# 13thISE_ver7.net
KiCad netlist of a schematic drawn in EAGLE
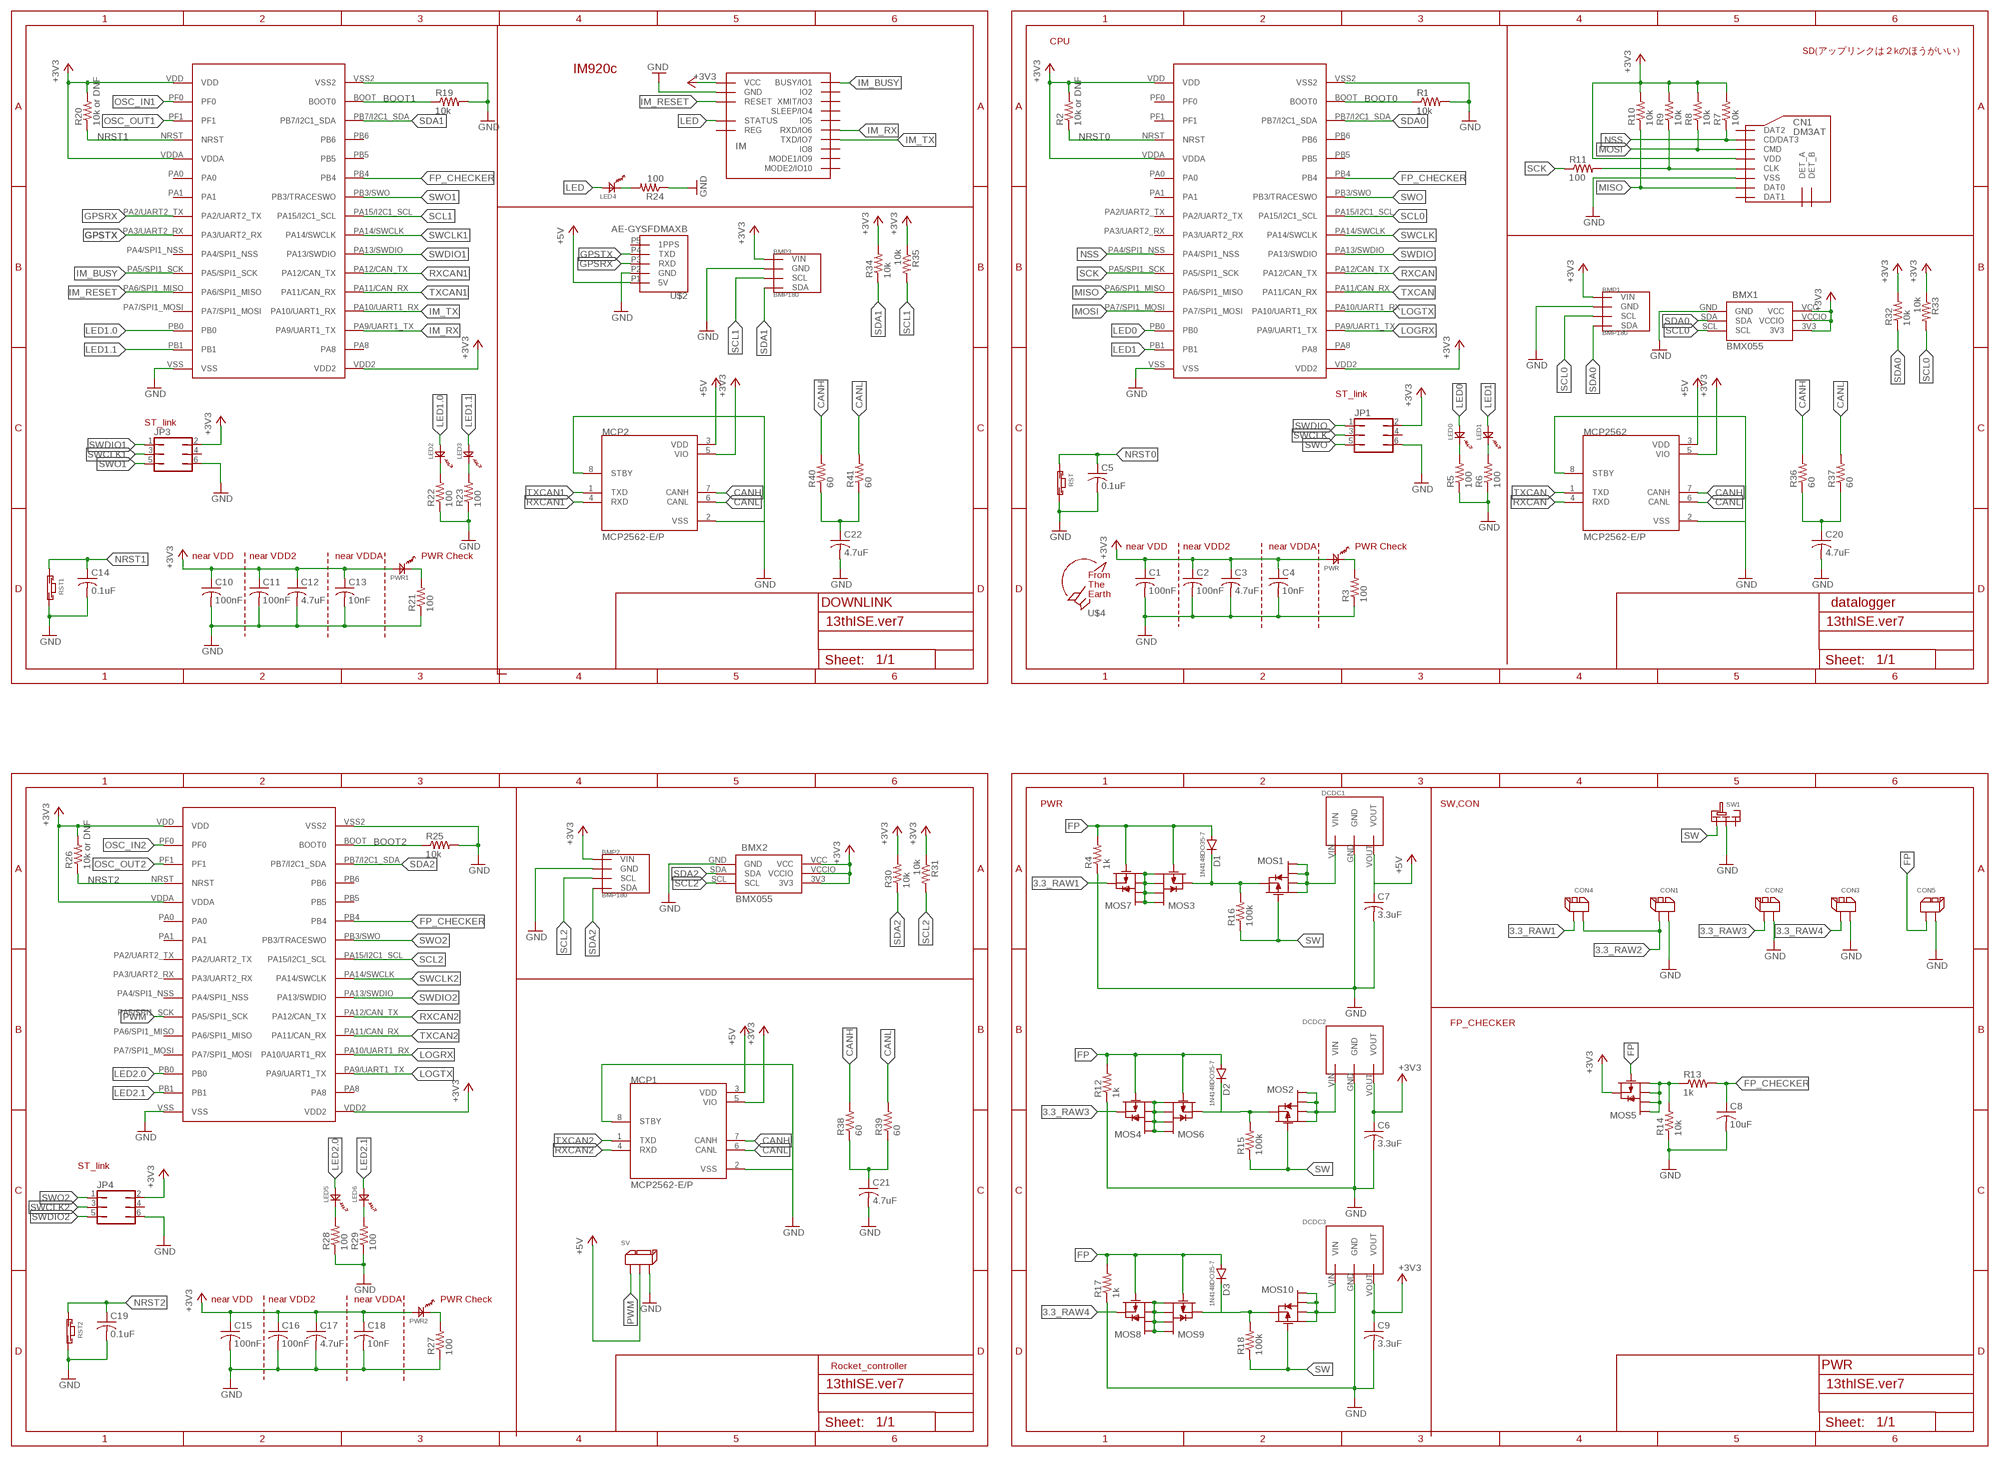
[diagram p0: schematic, sheet 1]

(export (version "E")
  (design (tool "Eeschema 10.0.6"))
  (components
    (comp (ref "BMP1")
      (value "BMP180")
      (footprint "eagle-import:GY-68")
      (libsource (lib "eagle-import") (part "BMP180"))
    )
    (comp (ref "BMP2")
      (value "BMP180")
      (footprint "eagle-import:GY-68")
      (libsource (lib "eagle-import") (part "BMP180"))
    )
    (comp (ref "BMP3")
      (value "BMP180")
      (footprint "eagle-import:GY-68")
      (libsource (lib "eagle-import") (part "BMP180"))
    )
    (comp (ref "BMX1")
      (value "BMX055")
      (footprint "eagle-import:BMX055")
      (libsource (lib "eagle-import") (part "BMX055"))
    )
    (comp (ref "BMX2")
      (value "BMX055")
      (footprint "eagle-import:BMX055")
      (libsource (lib "eagle-import") (part "BMX055"))
    )
    (comp (ref "C1")
      (value "100nF")
      (footprint "eagle-import:C1608")
      (libsource (lib "eagle-import") (part "C-USC1608"))
    )
    (comp (ref "C2")
      (value "100nF")
      (footprint "eagle-import:C1608")
      (libsource (lib "eagle-import") (part "C-USC1608"))
    )
    (comp (ref "C3")
      (value "4.7uF")
      (footprint "eagle-import:C1608")
      (libsource (lib "eagle-import") (part "C-USC1608"))
    )
    (comp (ref "C4")
      (value "10nF")
      (footprint "eagle-import:C1608")
      (libsource (lib "eagle-import") (part "C-USC1608"))
    )
    (comp (ref "C5")
      (value "0.1uF")
      (footprint "eagle-import:C1608")
      (libsource (lib "eagle-import") (part "C-USC1608"))
    )
    (comp (ref "C6")
      (value "3.3uF")
      (footprint "eagle-import:C0603")
      (libsource (lib "eagle-import") (part "C-USC0603"))
    )
    (comp (ref "C7")
      (value "3.3uF")
      (footprint "eagle-import:C0603")
      (libsource (lib "eagle-import") (part "C-USC0603"))
    )
    (comp (ref "C8")
      (value "10uF")
      (footprint "eagle-import:C0603")
      (libsource (lib "eagle-import") (part "C-USC0603"))
    )
    (comp (ref "C9")
      (value "3.3uF")
      (footprint "eagle-import:C0603")
      (libsource (lib "eagle-import") (part "C-USC0603"))
    )
    (comp (ref "C10")
      (value "100nF")
      (footprint "eagle-import:C1608")
      (libsource (lib "eagle-import") (part "C-USC1608"))
    )
    (comp (ref "C11")
      (value "100nF")
      (footprint "eagle-import:C1608")
      (libsource (lib "eagle-import") (part "C-USC1608"))
    )
    (comp (ref "C12")
      (value "4.7uF")
      (footprint "eagle-import:C1608")
      (libsource (lib "eagle-import") (part "C-USC1608"))
    )
    (comp (ref "C13")
      (value "10nF")
      (footprint "eagle-import:C1608")
      (libsource (lib "eagle-import") (part "C-USC1608"))
    )
    (comp (ref "C14")
      (value "0.1uF")
      (footprint "eagle-import:C1608")
      (libsource (lib "eagle-import") (part "C-USC1608"))
    )
    (comp (ref "C15")
      (value "100nF")
      (footprint "eagle-import:C1608")
      (libsource (lib "eagle-import") (part "C-USC1608"))
    )
    (comp (ref "C16")
      (value "100nF")
      (footprint "eagle-import:C1608")
      (libsource (lib "eagle-import") (part "C-USC1608"))
    )
    (comp (ref "C17")
      (value "4.7uF")
      (footprint "eagle-import:C1608")
      (libsource (lib "eagle-import") (part "C-USC1608"))
    )
    (comp (ref "C18")
      (value "10nF")
      (footprint "eagle-import:C1608")
      (libsource (lib "eagle-import") (part "C-USC1608"))
    )
    (comp (ref "C19")
      (value "0.1uF")
      (footprint "eagle-import:C1608")
      (libsource (lib "eagle-import") (part "C-USC1608"))
    )
    (comp (ref "C20")
      (value "4.7uF")
      (footprint "eagle-import:C0603")
      (libsource (lib "eagle-import") (part "C-USC0603"))
    )
    (comp (ref "C21")
      (value "4.7uF")
      (footprint "eagle-import:C0603")
      (libsource (lib "eagle-import") (part "C-USC0603"))
    )
    (comp (ref "C22")
      (value "4.7uF")
      (footprint "eagle-import:C0603")
      (libsource (lib "eagle-import") (part "C-USC0603"))
    )
    (comp (ref "CN1")
      (value "DM3AT")
      (footprint "eagle-import:DM3AT")
      (libsource (lib "eagle-import") (part "DM3AT"))
    )
    (comp (ref "CON1")
      (value "2PIN")
      (footprint "eagle-import:2PIN")
      (libsource (lib "eagle-import") (part "2PIN"))
    )
    (comp (ref "CON2")
      (value "2PIN")
      (footprint "eagle-import:2PIN")
      (libsource (lib "eagle-import") (part "2PIN"))
    )
    (comp (ref "CON3")
      (value "2PIN")
      (footprint "eagle-import:2PIN")
      (libsource (lib "eagle-import") (part "2PIN"))
    )
    (comp (ref "CON4")
      (value "2PIN")
      (footprint "eagle-import:2PIN")
      (libsource (lib "eagle-import") (part "2PIN"))
    )
    (comp (ref "CON5")
      (value "2PIN")
      (footprint "eagle-import:2PIN")
      (libsource (lib "eagle-import") (part "2PIN"))
    )
    (comp (ref "D1")
      (value "1N4148DO35-7")
      (footprint "eagle-import:DO35-7")
      (libsource (lib "eagle-import") (part "1N4148DO35-7"))
    )
    (comp (ref "D2")
      (value "1N4148DO35-7")
      (footprint "eagle-import:DO35-7")
      (libsource (lib "eagle-import") (part "1N4148DO35-7"))
    )
    (comp (ref "D3")
      (value "1N4148DO35-7")
      (footprint "eagle-import:DO35-7")
      (libsource (lib "eagle-import") (part "1N4148DO35-7"))
    )
    (comp (ref "DCDC1")
      (value "5V1A_M78AR05-1")
      (footprint "eagle-import:5V1A_M78AR05-1")
      (libsource (lib "eagle-import") (part "5V1A_M78AR05-1"))
    )
    (comp (ref "DCDC2")
      (value "3.3V1A_M78AR033-1")
      (footprint "eagle-import:3.3V1A_M78AR033-1")
      (libsource (lib "eagle-import") (part "3.3V1A_M78AR033-1"))
    )
    (comp (ref "DCDC3")
      (value "3.3V1A_M78AR033-1")
      (footprint "eagle-import:3.3V1A_M78AR033-1")
      (libsource (lib "eagle-import") (part "3.3V1A_M78AR033-1"))
    )
    (comp (ref "IM")
      (value "IM920C")
      (footprint "eagle-import:IM920C")
      (libsource (lib "eagle-import") (part "IM920C"))
    )
    (comp (ref "JP1")
      (value "JP3Q")
      (footprint "eagle-import:JP3Q")
      (libsource (lib "eagle-import") (part "JP3Q"))
    )
    (comp (ref "JP3")
      (value "JP3Q")
      (footprint "eagle-import:JP3Q")
      (libsource (lib "eagle-import") (part "JP3Q"))
    )
    (comp (ref "JP4")
      (value "JP3Q")
      (footprint "eagle-import:JP3Q")
      (libsource (lib "eagle-import") (part "JP3Q"))
    )
    (comp (ref "LED0")
      (value "OSXX1608C1A")
      (footprint "eagle-import:OSXX1608C1A")
      (libsource (lib "eagle-import") (part "OSXX1608C1A"))
    )
    (comp (ref "LED1")
      (value "OSXX1608C1A")
      (footprint "eagle-import:OSXX1608C1A")
      (libsource (lib "eagle-import") (part "OSXX1608C1A"))
    )
    (comp (ref "LED2")
      (value "OSXX1608C1A")
      (footprint "eagle-import:OSXX1608C1A")
      (libsource (lib "eagle-import") (part "OSXX1608C1A"))
    )
    (comp (ref "LED3")
      (value "OSXX1608C1A")
      (footprint "eagle-import:OSXX1608C1A")
      (libsource (lib "eagle-import") (part "OSXX1608C1A"))
    )
    (comp (ref "LED4")
      (value "OSXX1608C1A")
      (footprint "eagle-import:OSXX1608C1A")
      (libsource (lib "eagle-import") (part "OSXX1608C1A"))
    )
    (comp (ref "LED5")
      (value "OSXX1608C1A")
      (footprint "eagle-import:OSXX1608C1A")
      (libsource (lib "eagle-import") (part "OSXX1608C1A"))
    )
    (comp (ref "LED6")
      (value "OSXX1608C1A")
      (footprint "eagle-import:OSXX1608C1A")
      (libsource (lib "eagle-import") (part "OSXX1608C1A"))
    )
    (comp (ref "MCP1")
      (value "MCP2562-E/P")
      (footprint "eagle-import:DIP787W45P254L1016H533Q8")
      (fields (field (name "MF") "Microchip"))
      (libsource (lib "eagle-import") (part "MCP2562-E/P"))
    )
    (comp (ref "MCP2")
      (value "MCP2562-E/P")
      (footprint "eagle-import:DIP787W45P254L1016H533Q8")
      (fields (field (name "MF") "Microchip"))
      (libsource (lib "eagle-import") (part "MCP2562-E/P"))
    )
    (comp (ref "MCP2562")
      (value "MCP2562-E/P")
      (footprint "eagle-import:DIP787W45P254L1016H533Q8")
      (fields (field (name "MF") "Microchip"))
      (libsource (lib "eagle-import") (part "MCP2562-E/P"))
    )
    (comp (ref "MOS1")
      (value "PCH_SSM6J808R")
      (footprint "eagle-import:SSM6J808R")
      (libsource (lib "eagle-import") (part "PCH_SSM6J808R"))
    )
    (comp (ref "MOS2")
      (value "PCH_SSM6J808R")
      (footprint "eagle-import:SSM6J808R")
      (libsource (lib "eagle-import") (part "PCH_SSM6J808R"))
    )
    (comp (ref "MOS3")
      (value "PCH_SSM6J808R")
      (footprint "eagle-import:SSM6J808R")
      (libsource (lib "eagle-import") (part "PCH_SSM6J808R"))
    )
    (comp (ref "MOS4")
      (value "PCH_SSM6J808R")
      (footprint "eagle-import:SSM6J808R")
      (libsource (lib "eagle-import") (part "PCH_SSM6J808R"))
    )
    (comp (ref "MOS5")
      (value "PCH_SSM6J808R")
      (footprint "eagle-import:SSM6J808R")
      (libsource (lib "eagle-import") (part "PCH_SSM6J808R"))
    )
    (comp (ref "MOS6")
      (value "PCH_SSM6J808R")
      (footprint "eagle-import:SSM6J808R")
      (libsource (lib "eagle-import") (part "PCH_SSM6J808R"))
    )
    (comp (ref "MOS7")
      (value "PCH_SSM6J808R")
      (footprint "eagle-import:SSM6J808R")
      (libsource (lib "eagle-import") (part "PCH_SSM6J808R"))
    )
    (comp (ref "MOS8")
      (value "PCH_SSM6J808R")
      (footprint "eagle-import:SSM6J808R")
      (libsource (lib "eagle-import") (part "PCH_SSM6J808R"))
    )
    (comp (ref "MOS9")
      (value "PCH_SSM6J808R")
      (footprint "eagle-import:SSM6J808R")
      (libsource (lib "eagle-import") (part "PCH_SSM6J808R"))
    )
    (comp (ref "MOS10")
      (value "PCH_SSM6J808R")
      (footprint "eagle-import:SSM6J808R")
      (libsource (lib "eagle-import") (part "PCH_SSM6J808R"))
    )
    (comp (ref "PWR")
      (value "OSXX1608C1A")
      (footprint "eagle-import:OSXX1608C1A")
      (libsource (lib "eagle-import") (part "OSXX1608C1A"))
    )
    (comp (ref "PWR1")
      (value "OSXX1608C1A")
      (footprint "eagle-import:OSXX1608C1A")
      (libsource (lib "eagle-import") (part "OSXX1608C1A"))
    )
    (comp (ref "PWR2")
      (value "OSXX1608C1A")
      (footprint "eagle-import:OSXX1608C1A")
      (libsource (lib "eagle-import") (part "OSXX1608C1A"))
    )
    (comp (ref "R1")
      (value "10k")
      (footprint "eagle-import:R0603")
      (libsource (lib "eagle-import") (part "R-US_R0603"))
    )
    (comp (ref "R2")
      (value "10k or DNF")
      (footprint "eagle-import:R0603")
      (libsource (lib "eagle-import") (part "R-US_R0603"))
    )
    (comp (ref "R3")
      (value "100")
      (footprint "eagle-import:R0603")
      (libsource (lib "eagle-import") (part "R-US_R0603"))
    )
    (comp (ref "R4")
      (value "1k")
      (footprint "eagle-import:R0603")
      (libsource (lib "eagle-import") (part "R-US_R0603"))
    )
    (comp (ref "R5")
      (value "100")
      (footprint "eagle-import:R0603")
      (libsource (lib "eagle-import") (part "R-US_R0603"))
    )
    (comp (ref "R6")
      (value "100")
      (footprint "eagle-import:R0603")
      (libsource (lib "eagle-import") (part "R-US_R0603"))
    )
    (comp (ref "R7")
      (value "10k")
      (footprint "eagle-import:R0603")
      (libsource (lib "eagle-import") (part "R-US_R0603"))
    )
    (comp (ref "R8")
      (value "10k")
      (footprint "eagle-import:R0603")
      (libsource (lib "eagle-import") (part "R-US_R0603"))
    )
    (comp (ref "R9")
      (value "10k")
      (footprint "eagle-import:R0603")
      (libsource (lib "eagle-import") (part "R-US_R0603"))
    )
    (comp (ref "R10")
      (value "10k")
      (footprint "eagle-import:R0603")
      (libsource (lib "eagle-import") (part "R-US_R0603"))
    )
    (comp (ref "R11")
      (value "100")
      (footprint "eagle-import:R0603")
      (libsource (lib "eagle-import") (part "R-US_R0603"))
    )
    (comp (ref "R12")
      (value "1k")
      (footprint "eagle-import:R0603")
      (libsource (lib "eagle-import") (part "R-US_R0603"))
    )
    (comp (ref "R13")
      (value "1k")
      (footprint "eagle-import:R0603")
      (libsource (lib "eagle-import") (part "R-US_R0603"))
    )
    (comp (ref "R14")
      (value "10k")
      (footprint "eagle-import:R0603")
      (libsource (lib "eagle-import") (part "R-US_R0603"))
    )
    (comp (ref "R15")
      (value "100k")
      (footprint "eagle-import:R0603")
      (libsource (lib "eagle-import") (part "R-US_R0603"))
    )
    (comp (ref "R16")
      (value "100k")
      (footprint "eagle-import:R0603")
      (libsource (lib "eagle-import") (part "R-US_R0603"))
    )
    (comp (ref "R17")
      (value "1k")
      (footprint "eagle-import:R0603")
      (libsource (lib "eagle-import") (part "R-US_R0603"))
    )
    (comp (ref "R18")
      (value "100k")
      (footprint "eagle-import:R0603")
      (libsource (lib "eagle-import") (part "R-US_R0603"))
    )
    (comp (ref "R19")
      (value "10k")
      (footprint "eagle-import:R0603")
      (libsource (lib "eagle-import") (part "R-US_R0603"))
    )
    (comp (ref "R20")
      (value "10k or DNF")
      (footprint "eagle-import:R0603")
      (libsource (lib "eagle-import") (part "R-US_R0603"))
    )
    (comp (ref "R21")
      (value "100")
      (footprint "eagle-import:R0603")
      (libsource (lib "eagle-import") (part "R-US_R0603"))
    )
    (comp (ref "R22")
      (value "100")
      (footprint "eagle-import:R0603")
      (libsource (lib "eagle-import") (part "R-US_R0603"))
    )
    (comp (ref "R23")
      (value "100")
      (footprint "eagle-import:R0603")
      (libsource (lib "eagle-import") (part "R-US_R0603"))
    )
    (comp (ref "R24")
      (value "100")
      (footprint "eagle-import:R0603")
      (libsource (lib "eagle-import") (part "R-US_R0603"))
    )
    (comp (ref "R25")
      (value "10k")
      (footprint "eagle-import:R0603")
      (libsource (lib "eagle-import") (part "R-US_R0603"))
    )
    (comp (ref "R26")
      (value "10k or DNF")
      (footprint "eagle-import:R0603")
      (libsource (lib "eagle-import") (part "R-US_R0603"))
    )
    (comp (ref "R27")
      (value "100")
      (footprint "eagle-import:R0603")
      (libsource (lib "eagle-import") (part "R-US_R0603"))
    )
    (comp (ref "R28")
      (value "100")
      (footprint "eagle-import:R0603")
      (libsource (lib "eagle-import") (part "R-US_R0603"))
    )
    (comp (ref "R29")
      (value "100")
      (footprint "eagle-import:R0603")
      (libsource (lib "eagle-import") (part "R-US_R0603"))
    )
    (comp (ref "R30")
      (value "10k")
      (footprint "eagle-import:R0603")
      (libsource (lib "eagle-import") (part "R-US_R0603"))
    )
    (comp (ref "R31")
      (value "10k")
      (footprint "eagle-import:R0603")
      (libsource (lib "eagle-import") (part "R-US_R0603"))
    )
    (comp (ref "R32")
      (value "10k")
      (footprint "eagle-import:R0603")
      (libsource (lib "eagle-import") (part "R-US_R0603"))
    )
    (comp (ref "R33")
      (value "10k")
      (footprint "eagle-import:R0603")
      (libsource (lib "eagle-import") (part "R-US_R0603"))
    )
    (comp (ref "R34")
      (value "10k")
      (footprint "eagle-import:R0603")
      (libsource (lib "eagle-import") (part "R-US_R0603"))
    )
    (comp (ref "R35")
      (value "10k")
      (footprint "eagle-import:R0603")
      (libsource (lib "eagle-import") (part "R-US_R0603"))
    )
    (comp (ref "R36")
      (value "60")
      (footprint "eagle-import:R0603")
      (libsource (lib "eagle-import") (part "R-US_R0603"))
    )
    (comp (ref "R37")
      (value "60")
      (footprint "eagle-import:R0603")
      (libsource (lib "eagle-import") (part "R-US_R0603"))
    )
    (comp (ref "R38")
      (value "60")
      (footprint "eagle-import:R0603")
      (libsource (lib "eagle-import") (part "R-US_R0603"))
    )
    (comp (ref "R39")
      (value "60")
      (footprint "eagle-import:R0603")
      (libsource (lib "eagle-import") (part "R-US_R0603"))
    )
    (comp (ref "R40")
      (value "60")
      (footprint "eagle-import:R0603")
      (libsource (lib "eagle-import") (part "R-US_R0603"))
    )
    (comp (ref "R41")
      (value "60")
      (footprint "eagle-import:R0603")
      (libsource (lib "eagle-import") (part "R-US_R0603"))
    )
    (comp (ref "RST")
      (value "TVAF06-A020B-R")
      (footprint "eagle-import:TVAF06-A020B-R")
      (libsource (lib "eagle-import") (part "TVAF06-A020B-R"))
    )
    (comp (ref "RST1")
      (value "TVAF06-A020B-R")
      (footprint "eagle-import:TVAF06-A020B-R")
      (libsource (lib "eagle-import") (part "TVAF06-A020B-R"))
    )
    (comp (ref "RST2")
      (value "TVAF06-A020B-R")
      (footprint "eagle-import:TVAF06-A020B-R")
      (libsource (lib "eagle-import") (part "TVAF06-A020B-R"))
    )
    (comp (ref "STM0")
      (value "STM32F303K8")
      (footprint "eagle-import:STM32F303K8")
      (libsource (lib "eagle-import") (part "STM32F303K8"))
    )
    (comp (ref "STM1")
      (value "STM32F303K8")
      (footprint "eagle-import:STM32F303K8")
      (libsource (lib "eagle-import") (part "STM32F303K8"))
    )
    (comp (ref "SV")
      (value "3PIN")
      (footprint "eagle-import:3PIN")
      (libsource (lib "eagle-import") (part "3PIN"))
    )
    (comp (ref "SW1")
      (value "SRIDE_SWITCH")
      (footprint "eagle-import:SRIDE_SWITCH")
      (libsource (lib "eagle-import") (part "SRIDE_SWITCH"))
    )
    (comp (ref "U$1")
      (value "STM32F303K8")
      (footprint "eagle-import:STM32F303K8")
      (libsource (lib "eagle-import") (part "STM32F303K8"))
    )
    (comp (ref "U$2")
      (value "AE-GYSFDMAXB")
      (footprint "eagle-import:AE-GYSFDMAXB")
      (libsource (lib "eagle-import") (part "AE-GYSFDMAXB"))
    )
    (comp (ref "U$4")
      (value "F.T.E.LOGO")
      (footprint "eagle-import:LOGO")
      (libsource (lib "eagle-import") (part "F.T.E.LOGO"))
    )
  )
  (nets
    (net (code "1") (name "+3V3") (class "Default")
      (node (ref "BMP1") (pin "P1") (pinfunction "VIN_P1") (pintype "bidirectional"))
      (node (ref "BMP2") (pin "P1") (pinfunction "VIN_P1") (pintype "bidirectional"))
      (node (ref "BMP3") (pin "P1") (pinfunction "VIN_P1") (pintype "bidirectional"))
      (node (ref "BMX1") (pin "3V3") (pinfunction "3V3_3V3") (pintype "power_in"))
      (node (ref "BMX1") (pin "VCC") (pinfunction "VCC_VCC") (pintype "power_in"))
      (node (ref "BMX1") (pin "VCCIO") (pinfunction "VCCIO_VCCIO") (pintype "power_in"))
      (node (ref "BMX2") (pin "3V3") (pinfunction "3V3_3V3") (pintype "power_in"))
      (node (ref "BMX2") (pin "VCC") (pinfunction "VCC_VCC") (pintype "power_in"))
      (node (ref "BMX2") (pin "VCCIO") (pinfunction "VCCIO_VCCIO") (pintype "power_in"))
      (node (ref "C1") (pin "1") (pinfunction "1_1") (pintype "passive"))
      (node (ref "C10") (pin "1") (pinfunction "1_1") (pintype "passive"))
      (node (ref "C11") (pin "1") (pinfunction "1_1") (pintype "passive"))
      (node (ref "C12") (pin "1") (pinfunction "1_1") (pintype "passive"))
      (node (ref "C13") (pin "1") (pinfunction "1_1") (pintype "passive"))
      (node (ref "C15") (pin "1") (pinfunction "1_1") (pintype "passive"))
      (node (ref "C16") (pin "1") (pinfunction "1_1") (pintype "passive"))
      (node (ref "C17") (pin "1") (pinfunction "1_1") (pintype "passive"))
      (node (ref "C18") (pin "1") (pinfunction "1_1") (pintype "passive"))
      (node (ref "C2") (pin "1") (pinfunction "1_1") (pintype "passive"))
      (node (ref "C3") (pin "1") (pinfunction "1_1") (pintype "passive"))
      (node (ref "C4") (pin "1") (pinfunction "1_1") (pintype "passive"))
      (node (ref "C6") (pin "1") (pinfunction "1_1") (pintype "passive"))
      (node (ref "C9") (pin "1") (pinfunction "1_1") (pintype "passive"))
      (node (ref "CN1") (pin "VDD") (pinfunction "VDD_VDD") (pintype "bidirectional"))
      (node (ref "DCDC2") (pin "VOUT") (pinfunction "VOUT_VOUT") (pintype "bidirectional"))
      (node (ref "DCDC3") (pin "VOUT") (pinfunction "VOUT_VOUT") (pintype "bidirectional"))
      (node (ref "IM") (pin "$P17") (pinfunction "VCC_$P17") (pintype "bidirectional"))
      (node (ref "JP1") (pin "2") (pinfunction "2_2") (pintype "passive"))
      (node (ref "JP3") (pin "2") (pinfunction "2_2") (pintype "passive"))
      (node (ref "JP4") (pin "2") (pinfunction "2_2") (pintype "passive"))
      (node (ref "MCP1") (pin "5") (pinfunction "VIO_5") (pintype "power_in"))
      (node (ref "MCP2") (pin "5") (pinfunction "VIO_5") (pintype "power_in"))
      (node (ref "MCP2562") (pin "5") (pinfunction "VIO_5") (pintype "power_in"))
      (node (ref "MOS5") (pin "4") (pinfunction "4_4") (pintype "bidirectional"))
      (node (ref "PWR") (pin "AN") (pinfunction "AN_AN") (pintype "bidirectional"))
      (node (ref "PWR1") (pin "AN") (pinfunction "AN_AN") (pintype "bidirectional"))
      (node (ref "PWR2") (pin "AN") (pinfunction "AN_AN") (pintype "bidirectional"))
      (node (ref "R10") (pin "2") (pinfunction "2_2") (pintype "passive"))
      (node (ref "R2") (pin "2") (pinfunction "2_2") (pintype "passive"))
      (node (ref "R20") (pin "2") (pinfunction "2_2") (pintype "passive"))
      (node (ref "R26") (pin "2") (pinfunction "2_2") (pintype "passive"))
      (node (ref "R30") (pin "2") (pinfunction "2_2") (pintype "passive"))
      (node (ref "R31") (pin "1") (pinfunction "1_1") (pintype "passive"))
      (node (ref "R32") (pin "2") (pinfunction "2_2") (pintype "passive"))
      (node (ref "R33") (pin "1") (pinfunction "1_1") (pintype "passive"))
      (node (ref "R34") (pin "2") (pinfunction "2_2") (pintype "passive"))
      (node (ref "R35") (pin "1") (pinfunction "1_1") (pintype "passive"))
      (node (ref "R7") (pin "2") (pinfunction "2_2") (pintype "passive"))
      (node (ref "R8") (pin "2") (pinfunction "2_2") (pintype "passive"))
      (node (ref "R9") (pin "2") (pinfunction "2_2") (pintype "passive"))
      (node (ref "STM0") (pin "VDD") (pinfunction "VDD_VDD") (pintype "power_in"))
      (node (ref "STM0") (pin "VDD2") (pinfunction "VDD2_VDD2") (pintype "power_in"))
      (node (ref "STM0") (pin "VDDA") (pinfunction "VDDA_VDDA") (pintype "power_in"))
      (node (ref "STM1") (pin "VDD") (pinfunction "VDD_VDD") (pintype "power_in"))
      (node (ref "STM1") (pin "VDD2") (pinfunction "VDD2_VDD2") (pintype "power_in"))
      (node (ref "STM1") (pin "VDDA") (pinfunction "VDDA_VDDA") (pintype "power_in"))
      (node (ref "U$1") (pin "VDD") (pinfunction "VDD_VDD") (pintype "power_in"))
      (node (ref "U$1") (pin "VDD2") (pinfunction "VDD2_VDD2") (pintype "power_in"))
      (node (ref "U$1") (pin "VDDA") (pinfunction "VDDA_VDDA") (pintype "power_in"))
    )
    (net (code "2") (name "+5V") (class "Default")
      (node (ref "C7") (pin "1") (pinfunction "1_1") (pintype "passive"))
      (node (ref "DCDC1") (pin "VOUT") (pinfunction "VOUT_VOUT") (pintype "bidirectional"))
      (node (ref "MCP1") (pin "3") (pinfunction "VDD_3") (pintype "power_in"))
      (node (ref "MCP2") (pin "3") (pinfunction "VDD_3") (pintype "power_in"))
      (node (ref "MCP2562") (pin "3") (pinfunction "VDD_3") (pintype "power_in"))
      (node (ref "SV") (pin "P$2") (pinfunction "P$2_P$2") (pintype "bidirectional"))
      (node (ref "U$2") (pin "P1") (pinfunction "5V_P1") (pintype "bidirectional"))
    )
    (net (code "3") (name "/BOOT0") (class "Default")
      (node (ref "R1") (pin "1") (pinfunction "1_1") (pintype "passive"))
      (node (ref "STM0") (pin "BOOT") (pinfunction "BOOT0_BOOT") (pintype "bidirectional"))
    )
    (net (code "4") (name "/BOOT1") (class "Default")
      (node (ref "R19") (pin "1") (pinfunction "1_1") (pintype "passive"))
      (node (ref "STM1") (pin "BOOT") (pinfunction "BOOT0_BOOT") (pintype "bidirectional"))
    )
    (net (code "5") (name "/BOOT2") (class "Default")
      (node (ref "R25") (pin "1") (pinfunction "1_1") (pintype "passive"))
      (node (ref "U$1") (pin "BOOT") (pinfunction "BOOT0_BOOT") (pintype "bidirectional"))
    )
    (net (code "6") (name "3.3_RAW1") (class "Default")
      (node (ref "CON4") (pin "P$2") (pinfunction "P$2_P$2") (pintype "bidirectional"))
      (node (ref "MOS7") (pin "4") (pinfunction "4_4") (pintype "bidirectional"))
    )
    (net (code "7") (name "3.3_RAW2") (class "Default")
      (node (ref "CON1") (pin "P$2") (pinfunction "P$2_P$2") (pintype "bidirectional"))
      (node (ref "CON4") (pin "P$1") (pinfunction "P$1_P$1") (pintype "bidirectional"))
    )
    (net (code "8") (name "3.3_RAW3") (class "Default")
      (node (ref "CON2") (pin "P$2") (pinfunction "P$2_P$2") (pintype "bidirectional"))
      (node (ref "MOS4") (pin "4") (pinfunction "4_4") (pintype "bidirectional"))
    )
    (net (code "9") (name "3.3_RAW4") (class "Default")
      (node (ref "CON3") (pin "P$2") (pinfunction "P$2_P$2") (pintype "bidirectional"))
      (node (ref "MOS8") (pin "4") (pinfunction "4_4") (pintype "bidirectional"))
    )
    (net (code "10") (name "CANH") (class "Default")
      (node (ref "MCP1") (pin "7") (pinfunction "CANH_7") (pintype "bidirectional"))
      (node (ref "MCP2") (pin "7") (pinfunction "CANH_7") (pintype "bidirectional"))
      (node (ref "MCP2562") (pin "7") (pinfunction "CANH_7") (pintype "bidirectional"))
      (node (ref "R36") (pin "2") (pinfunction "2_2") (pintype "passive"))
      (node (ref "R38") (pin "2") (pinfunction "2_2") (pintype "passive"))
      (node (ref "R40") (pin "2") (pinfunction "2_2") (pintype "passive"))
    )
    (net (code "11") (name "CANL") (class "Default")
      (node (ref "MCP1") (pin "6") (pinfunction "CANL_6") (pintype "bidirectional"))
      (node (ref "MCP2") (pin "6") (pinfunction "CANL_6") (pintype "bidirectional"))
      (node (ref "MCP2562") (pin "6") (pinfunction "CANL_6") (pintype "bidirectional"))
      (node (ref "R37") (pin "2") (pinfunction "2_2") (pintype "passive"))
      (node (ref "R39") (pin "2") (pinfunction "2_2") (pintype "passive"))
      (node (ref "R41") (pin "2") (pinfunction "2_2") (pintype "passive"))
    )
    (net (code "12") (name "FP") (class "Default")
      (node (ref "CON5") (pin "P$1") (pinfunction "P$1_P$1") (pintype "bidirectional"))
      (node (ref "D1") (pin "A") (pinfunction "A_A") (pintype "passive"))
      (node (ref "D2") (pin "A") (pinfunction "A_A") (pintype "passive"))
      (node (ref "D3") (pin "A") (pinfunction "A_A") (pintype "passive"))
      (node (ref "MOS3") (pin "3") (pinfunction "3_3") (pintype "bidirectional"))
      (node (ref "MOS4") (pin "3") (pinfunction "3_3") (pintype "bidirectional"))
      (node (ref "MOS5") (pin "3") (pinfunction "3_3") (pintype "bidirectional"))
      (node (ref "MOS6") (pin "3") (pinfunction "3_3") (pintype "bidirectional"))
      (node (ref "MOS7") (pin "3") (pinfunction "3_3") (pintype "bidirectional"))
      (node (ref "MOS8") (pin "3") (pinfunction "3_3") (pintype "bidirectional"))
      (node (ref "MOS9") (pin "3") (pinfunction "3_3") (pintype "bidirectional"))
      (node (ref "R12") (pin "2") (pinfunction "2_2") (pintype "passive"))
      (node (ref "R17") (pin "2") (pinfunction "2_2") (pintype "passive"))
      (node (ref "R4") (pin "2") (pinfunction "2_2") (pintype "passive"))
    )
    (net (code "13") (name "FP_CHECKER") (class "Default")
      (node (ref "C8") (pin "1") (pinfunction "1_1") (pintype "passive"))
      (node (ref "R13") (pin "2") (pinfunction "2_2") (pintype "passive"))
      (node (ref "STM0") (pin "PB4") (pinfunction "PB4_PB4") (pintype "bidirectional"))
      (node (ref "STM1") (pin "PB4") (pinfunction "PB4_PB4") (pintype "bidirectional"))
      (node (ref "U$1") (pin "PB4") (pinfunction "PB4_PB4") (pintype "bidirectional"))
    )
    (net (code "14") (name "GND") (class "Default")
      (node (ref "BMP1") (pin "P2") (pinfunction "GND_P2") (pintype "bidirectional"))
      (node (ref "BMP2") (pin "P2") (pinfunction "GND_P2") (pintype "bidirectional"))
      (node (ref "BMP3") (pin "P2") (pinfunction "GND_P2") (pintype "bidirectional"))
      (node (ref "BMX1") (pin "GND") (pinfunction "GND_GND") (pintype "power_in"))
      (node (ref "BMX2") (pin "GND") (pinfunction "GND_GND") (pintype "power_in"))
      (node (ref "C1") (pin "2") (pinfunction "2_2") (pintype "passive"))
      (node (ref "C10") (pin "2") (pinfunction "2_2") (pintype "passive"))
      (node (ref "C11") (pin "2") (pinfunction "2_2") (pintype "passive"))
      (node (ref "C12") (pin "2") (pinfunction "2_2") (pintype "passive"))
      (node (ref "C13") (pin "2") (pinfunction "2_2") (pintype "passive"))
      (node (ref "C14") (pin "2") (pinfunction "2_2") (pintype "passive"))
      (node (ref "C15") (pin "2") (pinfunction "2_2") (pintype "passive"))
      (node (ref "C16") (pin "2") (pinfunction "2_2") (pintype "passive"))
      (node (ref "C17") (pin "2") (pinfunction "2_2") (pintype "passive"))
      (node (ref "C18") (pin "2") (pinfunction "2_2") (pintype "passive"))
      (node (ref "C19") (pin "2") (pinfunction "2_2") (pintype "passive"))
      (node (ref "C2") (pin "2") (pinfunction "2_2") (pintype "passive"))
      (node (ref "C20") (pin "2") (pinfunction "2_2") (pintype "passive"))
      (node (ref "C21") (pin "2") (pinfunction "2_2") (pintype "passive"))
      (node (ref "C22") (pin "2") (pinfunction "2_2") (pintype "passive"))
      (node (ref "C3") (pin "2") (pinfunction "2_2") (pintype "passive"))
      (node (ref "C4") (pin "2") (pinfunction "2_2") (pintype "passive"))
      (node (ref "C5") (pin "2") (pinfunction "2_2") (pintype "passive"))
      (node (ref "C6") (pin "2") (pinfunction "2_2") (pintype "passive"))
      (node (ref "C7") (pin "2") (pinfunction "2_2") (pintype "passive"))
      (node (ref "C8") (pin "2") (pinfunction "2_2") (pintype "passive"))
      (node (ref "C9") (pin "2") (pinfunction "2_2") (pintype "passive"))
      (node (ref "CN1") (pin "VSS") (pinfunction "VSS_VSS") (pintype "bidirectional"))
      (node (ref "CON1") (pin "P$1") (pinfunction "P$1_P$1") (pintype "bidirectional"))
      (node (ref "CON2") (pin "P$1") (pinfunction "P$1_P$1") (pintype "bidirectional"))
      (node (ref "CON3") (pin "P$1") (pinfunction "P$1_P$1") (pintype "bidirectional"))
      (node (ref "CON5") (pin "P$2") (pinfunction "P$2_P$2") (pintype "bidirectional"))
      (node (ref "DCDC1") (pin "GND") (pinfunction "GND_GND") (pintype "bidirectional"))
      (node (ref "DCDC2") (pin "GND") (pinfunction "GND_GND") (pintype "bidirectional"))
      (node (ref "DCDC3") (pin "GND") (pinfunction "GND_GND") (pintype "bidirectional"))
      (node (ref "IM") (pin "$P18") (pinfunction "GND_$P18") (pintype "bidirectional"))
      (node (ref "JP1") (pin "6") (pinfunction "6_6") (pintype "passive"))
      (node (ref "JP3") (pin "6") (pinfunction "6_6") (pintype "passive"))
      (node (ref "JP4") (pin "6") (pinfunction "6_6") (pintype "passive"))
      (node (ref "MCP1") (pin "2") (pinfunction "VSS_2") (pintype "power_in"))
      (node (ref "MCP1") (pin "8") (pinfunction "STBY_8") (pintype "input"))
      (node (ref "MCP2") (pin "2") (pinfunction "VSS_2") (pintype "power_in"))
      (node (ref "MCP2") (pin "8") (pinfunction "STBY_8") (pintype "input"))
      (node (ref "MCP2562") (pin "2") (pinfunction "VSS_2") (pintype "power_in"))
      (node (ref "MCP2562") (pin "8") (pinfunction "STBY_8") (pintype "input"))
      (node (ref "R1") (pin "2") (pinfunction "2_2") (pintype "passive"))
      (node (ref "R12") (pin "1") (pinfunction "1_1") (pintype "passive"))
      (node (ref "R14") (pin "1") (pinfunction "1_1") (pintype "passive"))
      (node (ref "R17") (pin "1") (pinfunction "1_1") (pintype "passive"))
      (node (ref "R19") (pin "2") (pinfunction "2_2") (pintype "passive"))
      (node (ref "R21") (pin "1") (pinfunction "1_1") (pintype "passive"))
      (node (ref "R22") (pin "1") (pinfunction "1_1") (pintype "passive"))
      (node (ref "R23") (pin "1") (pinfunction "1_1") (pintype "passive"))
      (node (ref "R24") (pin "1") (pinfunction "1_1") (pintype "passive"))
      (node (ref "R25") (pin "2") (pinfunction "2_2") (pintype "passive"))
      (node (ref "R27") (pin "1") (pinfunction "1_1") (pintype "passive"))
      (node (ref "R28") (pin "1") (pinfunction "1_1") (pintype "passive"))
      (node (ref "R29") (pin "1") (pinfunction "1_1") (pintype "passive"))
      (node (ref "R3") (pin "1") (pinfunction "1_1") (pintype "passive"))
      (node (ref "R4") (pin "1") (pinfunction "1_1") (pintype "passive"))
      (node (ref "R5") (pin "1") (pinfunction "1_1") (pintype "passive"))
      (node (ref "R6") (pin "1") (pinfunction "1_1") (pintype "passive"))
      (node (ref "RST") (pin "P$2") (pinfunction "P$2_P$2") (pintype "bidirectional"))
      (node (ref "RST1") (pin "P$2") (pinfunction "P$2_P$2") (pintype "bidirectional"))
      (node (ref "RST2") (pin "P$2") (pinfunction "P$2_P$2") (pintype "bidirectional"))
      (node (ref "STM0") (pin "VSS") (pinfunction "VSS_VSS") (pintype "power_in"))
      (node (ref "STM0") (pin "VSS2") (pinfunction "VSS2_VSS2") (pintype "power_in"))
      (node (ref "STM1") (pin "VSS") (pinfunction "VSS_VSS") (pintype "power_in"))
      (node (ref "STM1") (pin "VSS2") (pinfunction "VSS2_VSS2") (pintype "power_in"))
      (node (ref "SV") (pin "P$3") (pinfunction "P$3_P$3") (pintype "bidirectional"))
      (node (ref "SW1") (pin "LR") (pinfunction "LR_LR") (pintype "bidirectional"))
      (node (ref "U$1") (pin "VSS") (pinfunction "VSS_VSS") (pintype "power_in"))
      (node (ref "U$1") (pin "VSS2") (pinfunction "VSS2_VSS2") (pintype "power_in"))
      (node (ref "U$2") (pin "P2") (pinfunction "GND_P2") (pintype "bidirectional"))
    )
    (net (code "15") (name "GPSRX") (class "Default")
      (node (ref "STM1") (pin "PA2/UART2_TX") (pinfunction "PA2/UART2_TX_PA2/UART2_TX") (pintype "bidirectional"))
      (node (ref "U$2") (pin "P3") (pinfunction "RXD_P3") (pintype "bidirectional"))
    )
    (net (code "16") (name "GPSTX") (class "Default")
      (node (ref "STM1") (pin "PA3/UART2_RX") (pinfunction "PA3/UART2_RX_PA3/UART2_RX") (pintype "bidirectional"))
      (node (ref "U$2") (pin "P4") (pinfunction "TXD_P4") (pintype "bidirectional"))
    )
    (net (code "17") (name "IM_BUSY") (class "Default")
      (node (ref "IM") (pin "$P1") (pinfunction "BUSY/IO1_$P1") (pintype "bidirectional"))
      (node (ref "STM1") (pin "PA5/SPI1_SCK") (pinfunction "PA5/SPI1_SCK_PA5/SPI1_SCK") (pintype "bidirectional"))
    )
    (net (code "18") (name "IM_RESET") (class "Default")
      (node (ref "IM") (pin "$P19") (pinfunction "RESET_$P19") (pintype "bidirectional"))
      (node (ref "STM1") (pin "PA6/SPI1_MISO") (pinfunction "PA6/SPI1_MISO_PA6/SPI1_MISO") (pintype "bidirectional"))
    )
    (net (code "19") (name "IM_RX") (class "Default")
      (node (ref "IM") (pin "$P6") (pinfunction "RXD/IO6_$P6") (pintype "bidirectional"))
      (node (ref "STM1") (pin "PA9/UART1_TX") (pinfunction "PA9/UART1_TX_PA9/UART1_TX") (pintype "bidirectional"))
    )
    (net (code "20") (name "IM_TX") (class "Default")
      (node (ref "IM") (pin "$P7") (pinfunction "TXD/IO7_$P7") (pintype "bidirectional"))
      (node (ref "STM1") (pin "PA10/UART1_RX") (pinfunction "PA10/UART1_RX_PA10/UART1_RX") (pintype "bidirectional"))
    )
    (net (code "21") (name "LED") (class "Default")
      (node (ref "IM") (pin "$P15") (pinfunction "STATUS_$P15") (pintype "bidirectional"))
      (node (ref "LED4") (pin "AN") (pinfunction "AN_AN") (pintype "bidirectional"))
    )
    (net (code "22") (name "LED0") (class "Default")
      (node (ref "LED0") (pin "AN") (pinfunction "AN_AN") (pintype "bidirectional"))
      (node (ref "STM0") (pin "PB0") (pinfunction "PB0_PB0") (pintype "bidirectional"))
    )
    (net (code "23") (name "LED1") (class "Default")
      (node (ref "LED1") (pin "AN") (pinfunction "AN_AN") (pintype "bidirectional"))
      (node (ref "STM0") (pin "PB1") (pinfunction "PB1_PB1") (pintype "bidirectional"))
    )
    (net (code "24") (name "LED1.0") (class "Default")
      (node (ref "LED2") (pin "AN") (pinfunction "AN_AN") (pintype "bidirectional"))
      (node (ref "STM1") (pin "PB0") (pinfunction "PB0_PB0") (pintype "bidirectional"))
    )
    (net (code "25") (name "LED1.1") (class "Default")
      (node (ref "LED3") (pin "AN") (pinfunction "AN_AN") (pintype "bidirectional"))
      (node (ref "STM1") (pin "PB1") (pinfunction "PB1_PB1") (pintype "bidirectional"))
    )
    (net (code "26") (name "LED2.0") (class "Default")
      (node (ref "LED5") (pin "AN") (pinfunction "AN_AN") (pintype "bidirectional"))
      (node (ref "U$1") (pin "PB0") (pinfunction "PB0_PB0") (pintype "bidirectional"))
    )
    (net (code "27") (name "LED2.1") (class "Default")
      (node (ref "LED6") (pin "AN") (pinfunction "AN_AN") (pintype "bidirectional"))
      (node (ref "U$1") (pin "PB1") (pinfunction "PB1_PB1") (pintype "bidirectional"))
    )
    (net (code "28") (name "LOGRX") (class "Default")
      (node (ref "STM0") (pin "PA9/UART1_TX") (pinfunction "PA9/UART1_TX_PA9/UART1_TX") (pintype "bidirectional"))
      (node (ref "U$1") (pin "PA10/UART1_RX") (pinfunction "PA10/UART1_RX_PA10/UART1_RX") (pintype "bidirectional"))
    )
    (net (code "29") (name "LOGTX") (class "Default")
      (node (ref "STM0") (pin "PA10/UART1_RX") (pinfunction "PA10/UART1_RX_PA10/UART1_RX") (pintype "bidirectional"))
      (node (ref "U$1") (pin "PA9/UART1_TX") (pinfunction "PA9/UART1_TX_PA9/UART1_TX") (pintype "bidirectional"))
    )
    (net (code "30") (name "MISO") (class "Default")
      (node (ref "CN1") (pin "DAT0") (pinfunction "DAT0_DAT0") (pintype "bidirectional"))
      (node (ref "R10") (pin "1") (pinfunction "1_1") (pintype "passive"))
      (node (ref "STM0") (pin "PA6/SPI1_MISO") (pinfunction "PA6/SPI1_MISO_PA6/SPI1_MISO") (pintype "bidirectional"))
    )
    (net (code "31") (name "MOSI") (class "Default")
      (node (ref "CN1") (pin "CMD") (pinfunction "CMD_CMD") (pintype "bidirectional"))
      (node (ref "R8") (pin "1") (pinfunction "1_1") (pintype "passive"))
      (node (ref "STM0") (pin "PA7/SPI1_MOSI") (pinfunction "PA7/SPI1_MOSI_PA7/SPI1_MOSI") (pintype "bidirectional"))
    )
    (net (code "32") (name "NRST0") (class "Default")
      (node (ref "C5") (pin "1") (pinfunction "1_1") (pintype "passive"))
      (node (ref "R2") (pin "1") (pinfunction "1_1") (pintype "passive"))
      (node (ref "RST") (pin "P$1") (pinfunction "P$1_P$1") (pintype "bidirectional"))
      (node (ref "STM0") (pin "NRST") (pinfunction "NRST_NRST") (pintype "bidirectional"))
    )
    (net (code "33") (name "NRST1") (class "Default")
      (node (ref "C14") (pin "1") (pinfunction "1_1") (pintype "passive"))
      (node (ref "R20") (pin "1") (pinfunction "1_1") (pintype "passive"))
      (node (ref "RST1") (pin "P$1") (pinfunction "P$1_P$1") (pintype "bidirectional"))
      (node (ref "STM1") (pin "NRST") (pinfunction "NRST_NRST") (pintype "bidirectional"))
    )
    (net (code "34") (name "NRST2") (class "Default")
      (node (ref "C19") (pin "1") (pinfunction "1_1") (pintype "passive"))
      (node (ref "R26") (pin "1") (pinfunction "1_1") (pintype "passive"))
      (node (ref "RST2") (pin "P$1") (pinfunction "P$1_P$1") (pintype "bidirectional"))
      (node (ref "U$1") (pin "NRST") (pinfunction "NRST_NRST") (pintype "bidirectional"))
    )
    (net (code "35") (name "NSS") (class "Default")
      (node (ref "CN1") (pin "CD/DAT3") (pinfunction "CD/DAT3_CD/DAT3") (pintype "bidirectional"))
      (node (ref "R7") (pin "1") (pinfunction "1_1") (pintype "passive"))
      (node (ref "STM0") (pin "PA4/SPI1_NSS") (pinfunction "PA4/SPI1_NSS_PA4/SPI1_NSS") (pintype "bidirectional"))
    )
    (net (code "36") (name "Net-(C20-Pad1)") (class "Default")
      (node (ref "C20") (pin "1") (pinfunction "1_1") (pintype "passive"))
      (node (ref "R36") (pin "1") (pinfunction "1_1") (pintype "passive"))
      (node (ref "R37") (pin "1") (pinfunction "1_1") (pintype "passive"))
    )
    (net (code "37") (name "Net-(C21-Pad1)") (class "Default")
      (node (ref "C21") (pin "1") (pinfunction "1_1") (pintype "passive"))
      (node (ref "R38") (pin "1") (pinfunction "1_1") (pintype "passive"))
      (node (ref "R39") (pin "1") (pinfunction "1_1") (pintype "passive"))
    )
    (net (code "38") (name "Net-(C22-Pad1)") (class "Default")
      (node (ref "C22") (pin "1") (pinfunction "1_1") (pintype "passive"))
      (node (ref "R40") (pin "1") (pinfunction "1_1") (pintype "passive"))
      (node (ref "R41") (pin "1") (pinfunction "1_1") (pintype "passive"))
    )
    (net (code "39") (name "Net-(CN1-PadCLK)") (class "Default")
      (node (ref "CN1") (pin "CLK") (pinfunction "CLK_CLK") (pintype "bidirectional"))
      (node (ref "R11") (pin "2") (pinfunction "2_2") (pintype "passive"))
      (node (ref "R9") (pin "1") (pinfunction "1_1") (pintype "passive"))
    )
    (net (code "40") (name "Net-(D1-PadC)") (class "Default")
      (node (ref "D1") (pin "C") (pinfunction "C_C") (pintype "passive"))
      (node (ref "MOS1") (pin "4") (pinfunction "4_4") (pintype "bidirectional"))
      (node (ref "MOS3") (pin "4") (pinfunction "4_4") (pintype "bidirectional"))
      (node (ref "R16") (pin "2") (pinfunction "2_2") (pintype "passive"))
    )
    (net (code "41") (name "Net-(D2-PadC)") (class "Default")
      (node (ref "D2") (pin "C") (pinfunction "C_C") (pintype "passive"))
      (node (ref "MOS2") (pin "4") (pinfunction "4_4") (pintype "bidirectional"))
      (node (ref "MOS6") (pin "4") (pinfunction "4_4") (pintype "bidirectional"))
      (node (ref "R15") (pin "2") (pinfunction "2_2") (pintype "passive"))
    )
    (net (code "42") (name "Net-(D3-PadC)") (class "Default")
      (node (ref "D3") (pin "C") (pinfunction "C_C") (pintype "passive"))
      (node (ref "MOS10") (pin "4") (pinfunction "4_4") (pintype "bidirectional"))
      (node (ref "MOS9") (pin "4") (pinfunction "4_4") (pintype "bidirectional"))
      (node (ref "R18") (pin "2") (pinfunction "2_2") (pintype "passive"))
    )
    (net (code "43") (name "Net-(DCDC1-PadVIN)") (class "Default")
      (node (ref "DCDC1") (pin "VIN") (pinfunction "VIN_VIN") (pintype "bidirectional"))
      (node (ref "MOS1") (pin "1") (pinfunction "1_1") (pintype "bidirectional"))
      (node (ref "MOS1") (pin "2") (pinfunction "2_2") (pintype "bidirectional"))
      (node (ref "MOS1") (pin "5") (pinfunction "5_5") (pintype "bidirectional"))
      (node (ref "MOS1") (pin "6") (pinfunction "6_6") (pintype "bidirectional"))
    )
    (net (code "44") (name "Net-(DCDC2-PadVIN)") (class "Default")
      (node (ref "DCDC2") (pin "VIN") (pinfunction "VIN_VIN") (pintype "bidirectional"))
      (node (ref "MOS2") (pin "1") (pinfunction "1_1") (pintype "bidirectional"))
      (node (ref "MOS2") (pin "2") (pinfunction "2_2") (pintype "bidirectional"))
      (node (ref "MOS2") (pin "5") (pinfunction "5_5") (pintype "bidirectional"))
      (node (ref "MOS2") (pin "6") (pinfunction "6_6") (pintype "bidirectional"))
    )
    (net (code "45") (name "Net-(DCDC3-PadVIN)") (class "Default")
      (node (ref "DCDC3") (pin "VIN") (pinfunction "VIN_VIN") (pintype "bidirectional"))
      (node (ref "MOS10") (pin "1") (pinfunction "1_1") (pintype "bidirectional"))
      (node (ref "MOS10") (pin "2") (pinfunction "2_2") (pintype "bidirectional"))
      (node (ref "MOS10") (pin "5") (pinfunction "5_5") (pintype "bidirectional"))
      (node (ref "MOS10") (pin "6") (pinfunction "6_6") (pintype "bidirectional"))
    )
    (net (code "46") (name "Net-(LED0-PadCT)") (class "Default")
      (node (ref "LED0") (pin "CT") (pinfunction "CT_CT") (pintype "bidirectional"))
      (node (ref "R5") (pin "2") (pinfunction "2_2") (pintype "passive"))
    )
    (net (code "47") (name "Net-(LED1-PadCT)") (class "Default")
      (node (ref "LED1") (pin "CT") (pinfunction "CT_CT") (pintype "bidirectional"))
      (node (ref "R6") (pin "2") (pinfunction "2_2") (pintype "passive"))
    )
    (net (code "48") (name "Net-(LED2-PadCT)") (class "Default")
      (node (ref "LED2") (pin "CT") (pinfunction "CT_CT") (pintype "bidirectional"))
      (node (ref "R22") (pin "2") (pinfunction "2_2") (pintype "passive"))
    )
    (net (code "49") (name "Net-(LED3-PadCT)") (class "Default")
      (node (ref "LED3") (pin "CT") (pinfunction "CT_CT") (pintype "bidirectional"))
      (node (ref "R23") (pin "2") (pinfunction "2_2") (pintype "passive"))
    )
    (net (code "50") (name "Net-(LED4-PadCT)") (class "Default")
      (node (ref "LED4") (pin "CT") (pinfunction "CT_CT") (pintype "bidirectional"))
      (node (ref "R24") (pin "2") (pinfunction "2_2") (pintype "passive"))
    )
    (net (code "51") (name "Net-(LED5-PadCT)") (class "Default")
      (node (ref "LED5") (pin "CT") (pinfunction "CT_CT") (pintype "bidirectional"))
      (node (ref "R28") (pin "2") (pinfunction "2_2") (pintype "passive"))
    )
    (net (code "52") (name "Net-(LED6-PadCT)") (class "Default")
      (node (ref "LED6") (pin "CT") (pinfunction "CT_CT") (pintype "bidirectional"))
      (node (ref "R29") (pin "2") (pinfunction "2_2") (pintype "passive"))
    )
    (net (code "53") (name "Net-(MOS3-Pad1)") (class "Default")
      (node (ref "MOS3") (pin "1") (pinfunction "1_1") (pintype "bidirectional"))
      (node (ref "MOS3") (pin "2") (pinfunction "2_2") (pintype "bidirectional"))
      (node (ref "MOS3") (pin "5") (pinfunction "5_5") (pintype "bidirectional"))
      (node (ref "MOS3") (pin "6") (pinfunction "6_6") (pintype "bidirectional"))
      (node (ref "MOS7") (pin "1") (pinfunction "1_1") (pintype "bidirectional"))
      (node (ref "MOS7") (pin "2") (pinfunction "2_2") (pintype "bidirectional"))
      (node (ref "MOS7") (pin "5") (pinfunction "5_5") (pintype "bidirectional"))
      (node (ref "MOS7") (pin "6") (pinfunction "6_6") (pintype "bidirectional"))
    )
    (net (code "54") (name "Net-(MOS4-Pad1)") (class "Default")
      (node (ref "MOS4") (pin "1") (pinfunction "1_1") (pintype "bidirectional"))
      (node (ref "MOS4") (pin "2") (pinfunction "2_2") (pintype "bidirectional"))
      (node (ref "MOS4") (pin "5") (pinfunction "5_5") (pintype "bidirectional"))
      (node (ref "MOS4") (pin "6") (pinfunction "6_6") (pintype "bidirectional"))
      (node (ref "MOS6") (pin "1") (pinfunction "1_1") (pintype "bidirectional"))
      (node (ref "MOS6") (pin "2") (pinfunction "2_2") (pintype "bidirectional"))
      (node (ref "MOS6") (pin "5") (pinfunction "5_5") (pintype "bidirectional"))
      (node (ref "MOS6") (pin "6") (pinfunction "6_6") (pintype "bidirectional"))
    )
    (net (code "55") (name "Net-(MOS5-Pad1)") (class "Default")
      (node (ref "MOS5") (pin "1") (pinfunction "1_1") (pintype "bidirectional"))
      (node (ref "MOS5") (pin "2") (pinfunction "2_2") (pintype "bidirectional"))
      (node (ref "MOS5") (pin "5") (pinfunction "5_5") (pintype "bidirectional"))
      (node (ref "MOS5") (pin "6") (pinfunction "6_6") (pintype "bidirectional"))
      (node (ref "R13") (pin "1") (pinfunction "1_1") (pintype "passive"))
      (node (ref "R14") (pin "2") (pinfunction "2_2") (pintype "passive"))
    )
    (net (code "56") (name "Net-(MOS8-Pad1)") (class "Default")
      (node (ref "MOS8") (pin "1") (pinfunction "1_1") (pintype "bidirectional"))
      (node (ref "MOS8") (pin "2") (pinfunction "2_2") (pintype "bidirectional"))
      (node (ref "MOS8") (pin "5") (pinfunction "5_5") (pintype "bidirectional"))
      (node (ref "MOS8") (pin "6") (pinfunction "6_6") (pintype "bidirectional"))
      (node (ref "MOS9") (pin "1") (pinfunction "1_1") (pintype "bidirectional"))
      (node (ref "MOS9") (pin "2") (pinfunction "2_2") (pintype "bidirectional"))
      (node (ref "MOS9") (pin "5") (pinfunction "5_5") (pintype "bidirectional"))
      (node (ref "MOS9") (pin "6") (pinfunction "6_6") (pintype "bidirectional"))
    )
    (net (code "57") (name "Net-(PWR-PadCT)") (class "Default")
      (node (ref "PWR") (pin "CT") (pinfunction "CT_CT") (pintype "bidirectional"))
      (node (ref "R3") (pin "2") (pinfunction "2_2") (pintype "passive"))
    )
    (net (code "58") (name "Net-(PWR1-PadCT)") (class "Default")
      (node (ref "PWR1") (pin "CT") (pinfunction "CT_CT") (pintype "bidirectional"))
      (node (ref "R21") (pin "2") (pinfunction "2_2") (pintype "passive"))
    )
    (net (code "59") (name "Net-(PWR2-PadCT)") (class "Default")
      (node (ref "PWR2") (pin "CT") (pinfunction "CT_CT") (pintype "bidirectional"))
      (node (ref "R27") (pin "2") (pinfunction "2_2") (pintype "passive"))
    )
    (net (code "60") (name "OSC_IN1") (class "Default")
      (node (ref "STM1") (pin "PF0") (pinfunction "PF0_PF0") (pintype "bidirectional"))
    )
    (net (code "61") (name "OSC_IN2") (class "Default")
      (node (ref "U$1") (pin "PF0") (pinfunction "PF0_PF0") (pintype "bidirectional"))
    )
    (net (code "62") (name "OSC_OUT1") (class "Default")
      (node (ref "STM1") (pin "PF1") (pinfunction "PF1_PF1") (pintype "bidirectional"))
    )
    (net (code "63") (name "OSC_OUT2") (class "Default")
      (node (ref "U$1") (pin "PF1") (pinfunction "PF1_PF1") (pintype "bidirectional"))
    )
    (net (code "64") (name "PWM") (class "Default")
      (node (ref "SV") (pin "P$1") (pinfunction "P$1_P$1") (pintype "bidirectional"))
      (node (ref "U$1") (pin "PA5/SPI1_SCK") (pinfunction "PA5/SPI1_SCK_PA5/SPI1_SCK") (pintype "bidirectional"))
    )
    (net (code "65") (name "RXCAN") (class "Default")
      (node (ref "MCP2562") (pin "4") (pinfunction "RXD_4") (pintype "output"))
      (node (ref "STM0") (pin "PA12/CAN_TX") (pinfunction "PA12/CAN_TX_PA12/CAN_TX") (pintype "bidirectional"))
    )
    (net (code "66") (name "RXCAN1") (class "Default")
      (node (ref "MCP2") (pin "4") (pinfunction "RXD_4") (pintype "output"))
      (node (ref "STM1") (pin "PA12/CAN_TX") (pinfunction "PA12/CAN_TX_PA12/CAN_TX") (pintype "bidirectional"))
    )
    (net (code "67") (name "RXCAN2") (class "Default")
      (node (ref "MCP1") (pin "4") (pinfunction "RXD_4") (pintype "output"))
      (node (ref "U$1") (pin "PA12/CAN_TX") (pinfunction "PA12/CAN_TX_PA12/CAN_TX") (pintype "bidirectional"))
    )
    (net (code "68") (name "SCK") (class "Default")
      (node (ref "R11") (pin "1") (pinfunction "1_1") (pintype "passive"))
      (node (ref "STM0") (pin "PA5/SPI1_SCK") (pinfunction "PA5/SPI1_SCK_PA5/SPI1_SCK") (pintype "bidirectional"))
    )
    (net (code "69") (name "SCL0") (class "Default")
      (node (ref "BMP1") (pin "P3") (pinfunction "SCL_P3") (pintype "bidirectional"))
      (node (ref "BMX1") (pin "SCL") (pinfunction "SCL_SCL") (pintype "bidirectional"))
      (node (ref "R33") (pin "2") (pinfunction "2_2") (pintype "passive"))
      (node (ref "STM0") (pin "PA15/I2C1_SCL") (pinfunction "PA15/I2C1_SCL_PA15/I2C1_SCL") (pintype "bidirectional"))
    )
    (net (code "70") (name "SCL1") (class "Default")
      (node (ref "BMP3") (pin "P3") (pinfunction "SCL_P3") (pintype "bidirectional"))
      (node (ref "R35") (pin "2") (pinfunction "2_2") (pintype "passive"))
      (node (ref "STM1") (pin "PA15/I2C1_SCL") (pinfunction "PA15/I2C1_SCL_PA15/I2C1_SCL") (pintype "bidirectional"))
    )
    (net (code "71") (name "SCL2") (class "Default")
      (node (ref "BMP2") (pin "P3") (pinfunction "SCL_P3") (pintype "bidirectional"))
      (node (ref "BMX2") (pin "SCL") (pinfunction "SCL_SCL") (pintype "bidirectional"))
      (node (ref "R31") (pin "2") (pinfunction "2_2") (pintype "passive"))
      (node (ref "U$1") (pin "PA15/I2C1_SCL") (pinfunction "PA15/I2C1_SCL_PA15/I2C1_SCL") (pintype "bidirectional"))
    )
    (net (code "72") (name "SDA0") (class "Default")
      (node (ref "BMP1") (pin "P4") (pinfunction "SDA_P4") (pintype "bidirectional"))
      (node (ref "BMX1") (pin "SDA") (pinfunction "SDA_SDA") (pintype "bidirectional"))
      (node (ref "R32") (pin "1") (pinfunction "1_1") (pintype "passive"))
      (node (ref "STM0") (pin "PB7/I2C1_SDA") (pinfunction "PB7/I2C1_SDA_PB7/I2C1_SDA") (pintype "bidirectional"))
    )
    (net (code "73") (name "SDA1") (class "Default")
      (node (ref "BMP3") (pin "P4") (pinfunction "SDA_P4") (pintype "bidirectional"))
      (node (ref "R34") (pin "1") (pinfunction "1_1") (pintype "passive"))
      (node (ref "STM1") (pin "PB7/I2C1_SDA") (pinfunction "PB7/I2C1_SDA_PB7/I2C1_SDA") (pintype "bidirectional"))
    )
    (net (code "74") (name "SDA2") (class "Default")
      (node (ref "BMP2") (pin "P4") (pinfunction "SDA_P4") (pintype "bidirectional"))
      (node (ref "BMX2") (pin "SDA") (pinfunction "SDA_SDA") (pintype "bidirectional"))
      (node (ref "R30") (pin "1") (pinfunction "1_1") (pintype "passive"))
      (node (ref "U$1") (pin "PB7/I2C1_SDA") (pinfunction "PB7/I2C1_SDA_PB7/I2C1_SDA") (pintype "bidirectional"))
    )
    (net (code "75") (name "SW") (class "Default")
      (node (ref "MOS1") (pin "3") (pinfunction "3_3") (pintype "bidirectional"))
      (node (ref "MOS10") (pin "3") (pinfunction "3_3") (pintype "bidirectional"))
      (node (ref "MOS2") (pin "3") (pinfunction "3_3") (pintype "bidirectional"))
      (node (ref "R15") (pin "1") (pinfunction "1_1") (pintype "passive"))
      (node (ref "R16") (pin "1") (pinfunction "1_1") (pintype "passive"))
      (node (ref "R18") (pin "1") (pinfunction "1_1") (pintype "passive"))
      (node (ref "SW1") (pin "L") (pinfunction "L_L") (pintype "bidirectional"))
    )
    (net (code "76") (name "SWCLK") (class "Default")
      (node (ref "JP1") (pin "3") (pinfunction "3_3") (pintype "passive"))
      (node (ref "STM0") (pin "PA14/SWCLK") (pinfunction "PA14/SWCLK_PA14/SWCLK") (pintype "bidirectional"))
    )
    (net (code "77") (name "SWCLK1") (class "Default")
      (node (ref "JP3") (pin "3") (pinfunction "3_3") (pintype "passive"))
      (node (ref "STM1") (pin "PA14/SWCLK") (pinfunction "PA14/SWCLK_PA14/SWCLK") (pintype "bidirectional"))
    )
    (net (code "78") (name "SWCLK2") (class "Default")
      (node (ref "JP4") (pin "3") (pinfunction "3_3") (pintype "passive"))
      (node (ref "U$1") (pin "PA14/SWCLK") (pinfunction "PA14/SWCLK_PA14/SWCLK") (pintype "bidirectional"))
    )
    (net (code "79") (name "SWDIO") (class "Default")
      (node (ref "JP1") (pin "1") (pinfunction "1_1") (pintype "passive"))
      (node (ref "STM0") (pin "PA13/SWDIO") (pinfunction "PA13/SWDIO_PA13/SWDIO") (pintype "bidirectional"))
    )
    (net (code "80") (name "SWDIO1") (class "Default")
      (node (ref "JP3") (pin "1") (pinfunction "1_1") (pintype "passive"))
      (node (ref "STM1") (pin "PA13/SWDIO") (pinfunction "PA13/SWDIO_PA13/SWDIO") (pintype "bidirectional"))
    )
    (net (code "81") (name "SWDIO2") (class "Default")
      (node (ref "JP4") (pin "5") (pinfunction "5_5") (pintype "passive"))
      (node (ref "U$1") (pin "PA13/SWDIO") (pinfunction "PA13/SWDIO_PA13/SWDIO") (pintype "bidirectional"))
    )
    (net (code "82") (name "SWO") (class "Default")
      (node (ref "JP1") (pin "5") (pinfunction "5_5") (pintype "passive"))
      (node (ref "STM0") (pin "PB3/SWO") (pinfunction "PB3/TRACESWO_PB3/SWO") (pintype "bidirectional"))
    )
    (net (code "83") (name "SWO1") (class "Default")
      (node (ref "JP3") (pin "5") (pinfunction "5_5") (pintype "passive"))
      (node (ref "STM1") (pin "PB3/SWO") (pinfunction "PB3/TRACESWO_PB3/SWO") (pintype "bidirectional"))
    )
    (net (code "84") (name "SWO2") (class "Default")
      (node (ref "JP4") (pin "1") (pinfunction "1_1") (pintype "passive"))
      (node (ref "U$1") (pin "PB3/SWO") (pinfunction "PB3/TRACESWO_PB3/SWO") (pintype "bidirectional"))
    )
    (net (code "85") (name "TXCAN") (class "Default")
      (node (ref "MCP2562") (pin "1") (pinfunction "TXD_1") (pintype "input"))
      (node (ref "STM0") (pin "PA11/CAN_RX") (pinfunction "PA11/CAN_RX_PA11/CAN_RX") (pintype "bidirectional"))
    )
    (net (code "86") (name "TXCAN1") (class "Default")
      (node (ref "MCP2") (pin "1") (pinfunction "TXD_1") (pintype "input"))
      (node (ref "STM1") (pin "PA11/CAN_RX") (pinfunction "PA11/CAN_RX_PA11/CAN_RX") (pintype "bidirectional"))
    )
    (net (code "87") (name "TXCAN2") (class "Default")
      (node (ref "MCP1") (pin "1") (pinfunction "TXD_1") (pintype "input"))
      (node (ref "U$1") (pin "PA11/CAN_RX") (pinfunction "PA11/CAN_RX_PA11/CAN_RX") (pintype "bidirectional"))
    )
    (net (code "88") (name "unconnected-(CN1-PadDAT1)") (class "Default")
      (node (ref "CN1") (pin "DAT1") (pinfunction "DAT1_DAT1") (pintype "bidirectional"))
    )
    (net (code "89") (name "unconnected-(CN1-PadDAT2)") (class "Default")
      (node (ref "CN1") (pin "DAT2") (pinfunction "DAT2_DAT2") (pintype "bidirectional"))
    )
    (net (code "90") (name "unconnected-(CN1-PadDET_A)") (class "Default")
      (node (ref "CN1") (pin "DET_A") (pinfunction "DET_A_DET_A") (pintype "bidirectional"))
    )
    (net (code "91") (name "unconnected-(CN1-PadDET_B)") (class "Default")
      (node (ref "CN1") (pin "DET_B") (pinfunction "DET_B_DET_B") (pintype "bidirectional"))
    )
    (net (code "92") (name "unconnected-(IM-IO2-Pad$P2)") (class "Default")
      (node (ref "IM") (pin "$P2") (pinfunction "IO2_$P2") (pintype "bidirectional"))
    )
    (net (code "93") (name "unconnected-(IM-IO5-Pad$P5)") (class "Default")
      (node (ref "IM") (pin "$P5") (pinfunction "IO5_$P5") (pintype "bidirectional"))
    )
    (net (code "94") (name "unconnected-(IM-IO8-Pad$P8)") (class "Default")
      (node (ref "IM") (pin "$P8") (pinfunction "IO8_$P8") (pintype "bidirectional"))
    )
    (net (code "95") (name "unconnected-(IM-MODE1{slash}IO9-Pad$P9)") (class "Default")
      (node (ref "IM") (pin "$P9") (pinfunction "MODE1/IO9_$P9") (pintype "bidirectional"))
    )
    (net (code "96") (name "unconnected-(IM-MODE2{slash}IO10-Pad$P10)") (class "Default")
      (node (ref "IM") (pin "$P10") (pinfunction "MODE2/IO10_$P10") (pintype "bidirectional"))
    )
    (net (code "97") (name "unconnected-(IM-REG-Pad$P16)") (class "Default")
      (node (ref "IM") (pin "$P16") (pinfunction "REG_$P16") (pintype "bidirectional"))
    )
    (net (code "98") (name "unconnected-(IM-SLEEP{slash}IO4-Pad$P4)") (class "Default")
      (node (ref "IM") (pin "$P4") (pinfunction "SLEEP/IO4_$P4") (pintype "bidirectional"))
    )
    (net (code "99") (name "unconnected-(IM-XMIT{slash}IO3-Pad$P3)") (class "Default")
      (node (ref "IM") (pin "$P3") (pinfunction "XMIT/IO3_$P3") (pintype "bidirectional"))
    )
    (net (code "100") (name "unconnected-(JP1-Pad4)") (class "Default")
      (node (ref "JP1") (pin "4") (pinfunction "4_4") (pintype "passive"))
    )
    (net (code "101") (name "unconnected-(JP3-Pad4)") (class "Default")
      (node (ref "JP3") (pin "4") (pinfunction "4_4") (pintype "passive"))
    )
    (net (code "102") (name "unconnected-(JP4-Pad4)") (class "Default")
      (node (ref "JP4") (pin "4") (pinfunction "4_4") (pintype "passive"))
    )
    (net (code "103") (name "unconnected-(STM0-PadPA0)") (class "Default")
      (node (ref "STM0") (pin "PA0") (pinfunction "PA0_PA0") (pintype "bidirectional"))
    )
    (net (code "104") (name "unconnected-(STM0-PadPA1)") (class "Default")
      (node (ref "STM0") (pin "PA1") (pinfunction "PA1_PA1") (pintype "bidirectional"))
    )
    (net (code "105") (name "unconnected-(STM0-PadPA2{slash}UART2_TX)") (class "Default")
      (node (ref "STM0") (pin "PA2/UART2_TX") (pinfunction "PA2/UART2_TX_PA2/UART2_TX") (pintype "bidirectional"))
    )
    (net (code "106") (name "unconnected-(STM0-PadPA3{slash}UART2_RX)") (class "Default")
      (node (ref "STM0") (pin "PA3/UART2_RX") (pinfunction "PA3/UART2_RX_PA3/UART2_RX") (pintype "bidirectional"))
    )
    (net (code "107") (name "unconnected-(STM0-PadPA8)") (class "Default")
      (node (ref "STM0") (pin "PA8") (pinfunction "PA8_PA8") (pintype "bidirectional"))
    )
    (net (code "108") (name "unconnected-(STM0-PadPB5)") (class "Default")
      (node (ref "STM0") (pin "PB5") (pinfunction "PB5_PB5") (pintype "bidirectional"))
    )
    (net (code "109") (name "unconnected-(STM0-PadPB6)") (class "Default")
      (node (ref "STM0") (pin "PB6") (pinfunction "PB6_PB6") (pintype "bidirectional"))
    )
    (net (code "110") (name "unconnected-(STM0-PadPF0)") (class "Default")
      (node (ref "STM0") (pin "PF0") (pinfunction "PF0_PF0") (pintype "bidirectional"))
    )
    (net (code "111") (name "unconnected-(STM0-PadPF1)") (class "Default")
      (node (ref "STM0") (pin "PF1") (pinfunction "PF1_PF1") (pintype "bidirectional"))
    )
    (net (code "112") (name "unconnected-(STM1-PadPA0)") (class "Default")
      (node (ref "STM1") (pin "PA0") (pinfunction "PA0_PA0") (pintype "bidirectional"))
    )
    (net (code "113") (name "unconnected-(STM1-PadPA1)") (class "Default")
      (node (ref "STM1") (pin "PA1") (pinfunction "PA1_PA1") (pintype "bidirectional"))
    )
    (net (code "114") (name "unconnected-(STM1-PadPA4{slash}SPI1_NSS)") (class "Default")
      (node (ref "STM1") (pin "PA4/SPI1_NSS") (pinfunction "PA4/SPI1_NSS_PA4/SPI1_NSS") (pintype "bidirectional"))
    )
    (net (code "115") (name "unconnected-(STM1-PadPA7{slash}SPI1_MOSI)") (class "Default")
      (node (ref "STM1") (pin "PA7/SPI1_MOSI") (pinfunction "PA7/SPI1_MOSI_PA7/SPI1_MOSI") (pintype "bidirectional"))
    )
    (net (code "116") (name "unconnected-(STM1-PadPA8)") (class "Default")
      (node (ref "STM1") (pin "PA8") (pinfunction "PA8_PA8") (pintype "bidirectional"))
    )
    (net (code "117") (name "unconnected-(STM1-PadPB5)") (class "Default")
      (node (ref "STM1") (pin "PB5") (pinfunction "PB5_PB5") (pintype "bidirectional"))
    )
    (net (code "118") (name "unconnected-(STM1-PadPB6)") (class "Default")
      (node (ref "STM1") (pin "PB6") (pinfunction "PB6_PB6") (pintype "bidirectional"))
    )
    (net (code "119") (name "unconnected-(SW1-PadR)") (class "Default")
      (node (ref "SW1") (pin "R") (pinfunction "R_R") (pintype "bidirectional"))
    )
    (net (code "120") (name "unconnected-(U$1-PadPA0)") (class "Default")
      (node (ref "U$1") (pin "PA0") (pinfunction "PA0_PA0") (pintype "bidirectional"))
    )
    (net (code "121") (name "unconnected-(U$1-PadPA1)") (class "Default")
      (node (ref "U$1") (pin "PA1") (pinfunction "PA1_PA1") (pintype "bidirectional"))
    )
    (net (code "122") (name "unconnected-(U$1-PadPA2{slash}UART2_TX)") (class "Default")
      (node (ref "U$1") (pin "PA2/UART2_TX") (pinfunction "PA2/UART2_TX_PA2/UART2_TX") (pintype "bidirectional"))
    )
    (net (code "123") (name "unconnected-(U$1-PadPA3{slash}UART2_RX)") (class "Default")
      (node (ref "U$1") (pin "PA3/UART2_RX") (pinfunction "PA3/UART2_RX_PA3/UART2_RX") (pintype "bidirectional"))
    )
    (net (code "124") (name "unconnected-(U$1-PadPA4{slash}SPI1_NSS)") (class "Default")
      (node (ref "U$1") (pin "PA4/SPI1_NSS") (pinfunction "PA4/SPI1_NSS_PA4/SPI1_NSS") (pintype "bidirectional"))
    )
    (net (code "125") (name "unconnected-(U$1-PadPA6{slash}SPI1_MISO)") (class "Default")
      (node (ref "U$1") (pin "PA6/SPI1_MISO") (pinfunction "PA6/SPI1_MISO_PA6/SPI1_MISO") (pintype "bidirectional"))
    )
    (net (code "126") (name "unconnected-(U$1-PadPA7{slash}SPI1_MOSI)") (class "Default")
      (node (ref "U$1") (pin "PA7/SPI1_MOSI") (pinfunction "PA7/SPI1_MOSI_PA7/SPI1_MOSI") (pintype "bidirectional"))
    )
    (net (code "127") (name "unconnected-(U$1-PadPA8)") (class "Default")
      (node (ref "U$1") (pin "PA8") (pinfunction "PA8_PA8") (pintype "bidirectional"))
    )
    (net (code "128") (name "unconnected-(U$1-PadPB5)") (class "Default")
      (node (ref "U$1") (pin "PB5") (pinfunction "PB5_PB5") (pintype "bidirectional"))
    )
    (net (code "129") (name "unconnected-(U$1-PadPB6)") (class "Default")
      (node (ref "U$1") (pin "PB6") (pinfunction "PB6_PB6") (pintype "bidirectional"))
    )
    (net (code "130") (name "unconnected-(U$2-1PPS-PadP5)") (class "Default")
      (node (ref "U$2") (pin "P5") (pinfunction "1PPS_P5") (pintype "bidirectional"))
    )
  )
)
